# SCH_USB_hub_2024-10-11.net
KiCad netlist of a schematic drawn in EasyEDA
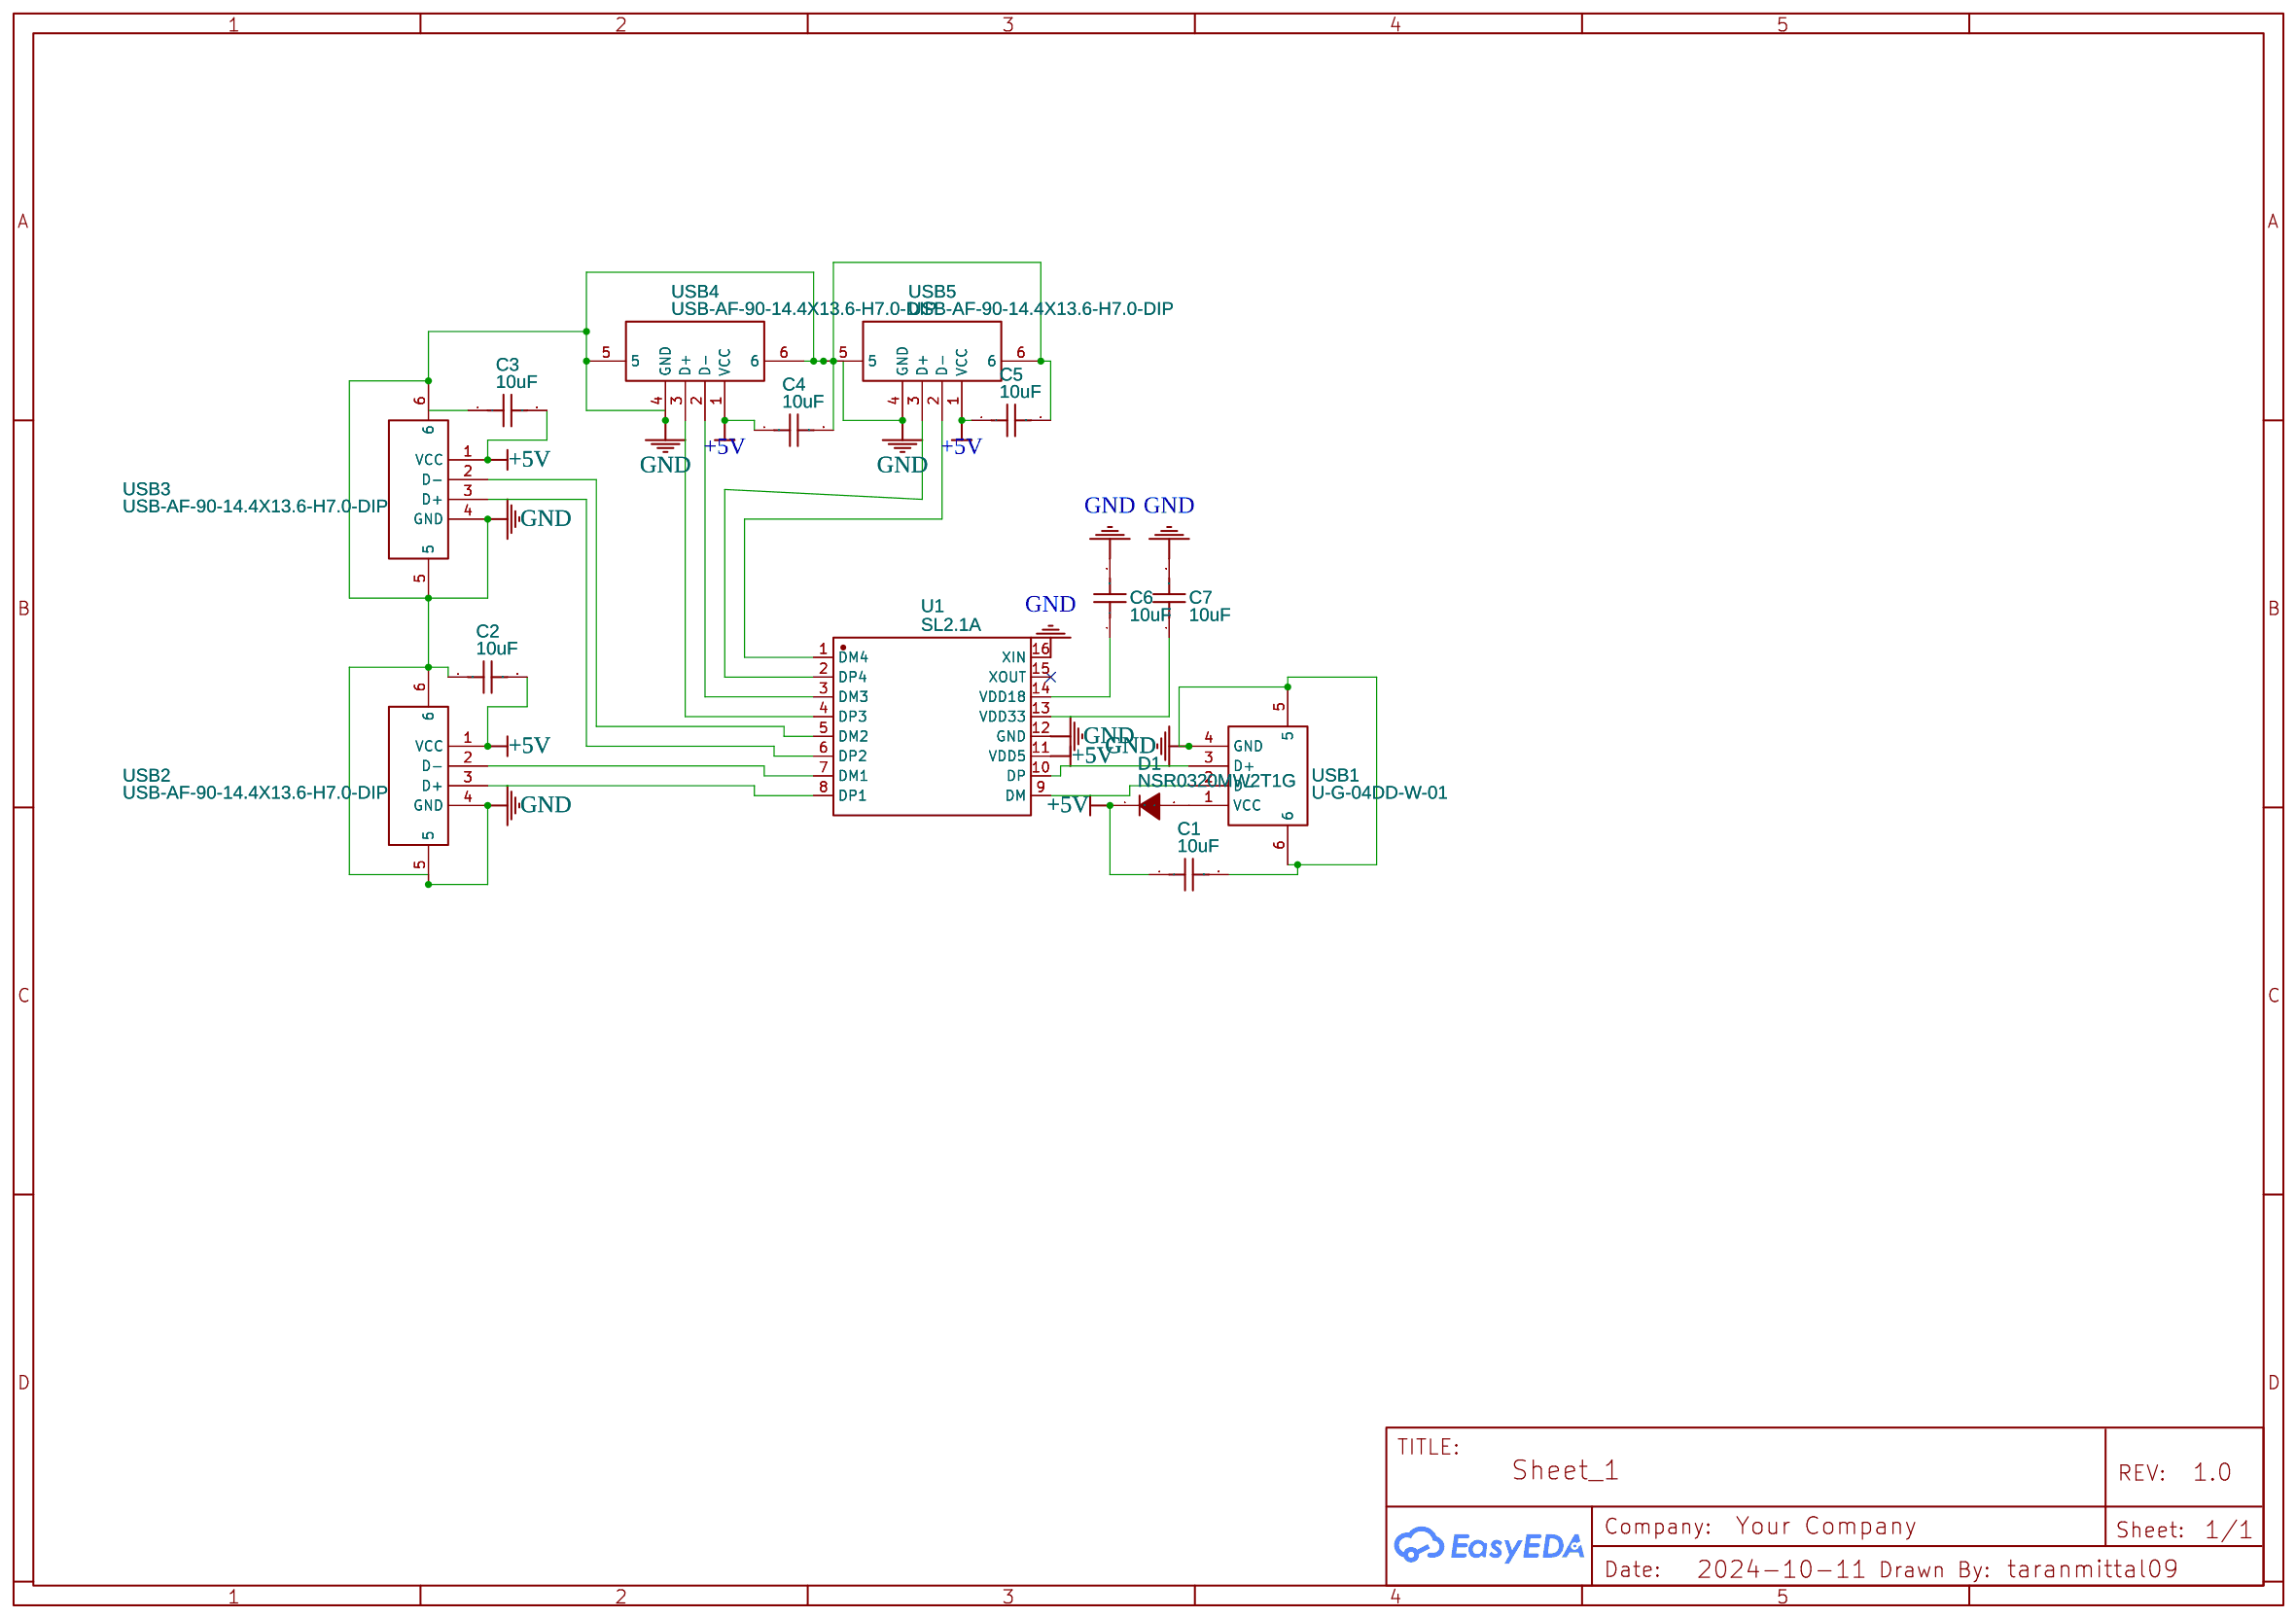
[diagram p0: schematic sheet]

(export (version "E")
  (design (tool "Eeschema 10.0.6"))
  (components
    (comp (ref "C1")
      (value "10uF")
      (fields
        (field (name "Manufacturer Part") "CL10A106KP8NNNC")
        (field (name "Manufacturer") "SAMSUNG(三星)")
      )
      (libsource (lib "") (part "CL10A106KP8NNNC"))
    )
    (comp (ref "C2")
      (value "10uF")
      (fields
        (field (name "Manufacturer Part") "CL10A106KP8NNNC")
        (field (name "Manufacturer") "SAMSUNG(三星)")
      )
      (libsource (lib "") (part "CL10A106KP8NNNC"))
    )
    (comp (ref "C3")
      (value "10uF")
      (fields
        (field (name "Manufacturer Part") "CL10A106KP8NNNC")
        (field (name "Manufacturer") "SAMSUNG(三星)")
      )
      (libsource (lib "") (part "CL10A106KP8NNNC"))
    )
    (comp (ref "C4")
      (value "10uF")
      (fields
        (field (name "Manufacturer Part") "CL10A106KP8NNNC")
        (field (name "Manufacturer") "SAMSUNG(三星)")
      )
      (libsource (lib "") (part "CL10A106KP8NNNC"))
    )
    (comp (ref "C5")
      (value "10uF")
      (fields
        (field (name "Manufacturer Part") "CL10A106KP8NNNC")
        (field (name "Manufacturer") "SAMSUNG(三星)")
      )
      (libsource (lib "") (part "CL10A106KP8NNNC"))
    )
    (comp (ref "C6")
      (value "10uF")
      (fields
        (field (name "Manufacturer Part") "CL10A106KP8NNNC")
        (field (name "Manufacturer") "SAMSUNG(三星)")
      )
      (libsource (lib "") (part "CL10A106KP8NNNC_1"))
    )
    (comp (ref "C7")
      (value "10uF")
      (fields
        (field (name "Manufacturer Part") "CL10A106KP8NNNC")
        (field (name "Manufacturer") "SAMSUNG(三星)")
      )
      (libsource (lib "") (part "CL10A106KP8NNNC_1"))
    )
    (comp (ref "D1")
      (value "NSR0320MW2T1G")
      (fields (field (name "Manufacturer") "onsemi(安森美)"))
      (libsource (lib "") (part "NSR0320MW2T1G"))
    )
    (comp (ref "U1")
      (value "SL2.1A")
      (fields (field (name "Manufacturer") "CoreChips(和芯润德)"))
      (libsource (lib "") (part "SL2.1A"))
    )
    (comp (ref "USB1")
      (value "U-G-04DD-W-01")
      (fields (field (name "Manufacturer Part") "U-G-O4DD-W-1") (field (name "Manufacturer") "韩国韩荣"))
      (libsource (lib "") (part "U-G-04DD-W-01"))
    )
    (comp (ref "USB2")
      (value "USB-AF-90-14.4X13.6-H7.0-DIP")
      (fields (field (name "Manufacturer Part") "903-131A1011D10100") (field (name "Manufacturer") "精拓金"))
      (libsource (lib "") (part "USB-AF-90-14.4X13.6-H7.0-DIP"))
    )
    (comp (ref "USB3")
      (value "USB-AF-90-14.4X13.6-H7.0-DIP")
      (fields (field (name "Manufacturer Part") "903-131A1011D10100") (field (name "Manufacturer") "精拓金"))
      (libsource (lib "") (part "USB-AF-90-14.4X13.6-H7.0-DIP"))
    )
    (comp (ref "USB4")
      (value "USB-AF-90-14.4X13.6-H7.0-DIP")
      (fields (field (name "Manufacturer Part") "903-131A1011D10100") (field (name "Manufacturer") "精拓金"))
      (libsource (lib "") (part "USB-AF-90-14.4X13.6-H7.0-DIP_1"))
    )
    (comp (ref "USB5")
      (value "USB-AF-90-14.4X13.6-H7.0-DIP")
      (fields (field (name "Manufacturer Part") "903-131A1011D10100") (field (name "Manufacturer") "精拓金"))
      (libsource (lib "") (part "USB-AF-90-14.4X13.6-H7.0-DIP_1"))
    )
  )
  (nets
    (net (code "1") (name "+5V") (class "Default")
      (node (ref "C1") (pin "1") (pinfunction "1_1") (pintype "unspecified"))
      (node (ref "C2") (pin "2") (pinfunction "2_2") (pintype "unspecified"))
      (node (ref "C3") (pin "2") (pinfunction "2_2") (pintype "unspecified"))
      (node (ref "C4") (pin "1") (pinfunction "1_1") (pintype "unspecified"))
      (node (ref "C5") (pin "1") (pinfunction "1_1") (pintype "unspecified"))
      (node (ref "D1") (pin "1") (pinfunction "C_1") (pintype "unspecified"))
      (node (ref "U1") (pin "11") (pinfunction "VDD5_11") (pintype "unspecified"))
      (node (ref "USB2") (pin "1") (pinfunction "VCC_1") (pintype "unspecified"))
      (node (ref "USB3") (pin "1") (pinfunction "VCC_1") (pintype "unspecified"))
      (node (ref "USB4") (pin "1") (pinfunction "VCC_1") (pintype "unspecified"))
      (node (ref "USB5") (pin "1") (pinfunction "VCC_1") (pintype "unspecified"))
    )
    (net (code "2") (name "GND") (class "Default")
      (node (ref "C1") (pin "2") (pinfunction "2_2") (pintype "unspecified"))
      (node (ref "C2") (pin "1") (pinfunction "1_1") (pintype "unspecified"))
      (node (ref "C3") (pin "1") (pinfunction "1_1") (pintype "unspecified"))
      (node (ref "C4") (pin "2") (pinfunction "2_2") (pintype "unspecified"))
      (node (ref "C5") (pin "2") (pinfunction "2_2") (pintype "unspecified"))
      (node (ref "C6") (pin "2") (pinfunction "2_2") (pintype "unspecified"))
      (node (ref "C7") (pin "2") (pinfunction "2_2") (pintype "unspecified"))
      (node (ref "U1") (pin "12") (pinfunction "GND_12") (pintype "unspecified"))
      (node (ref "U1") (pin "16") (pinfunction "XIN_16") (pintype "unspecified"))
      (node (ref "USB1") (pin "4") (pinfunction "GND_4") (pintype "unspecified"))
      (node (ref "USB1") (pin "5") (pinfunction "5_5") (pintype "unspecified"))
      (node (ref "USB1") (pin "6") (pinfunction "6_6") (pintype "unspecified"))
      (node (ref "USB2") (pin "4") (pinfunction "GND_4") (pintype "unspecified"))
      (node (ref "USB2") (pin "5") (pinfunction "5_5") (pintype "unspecified"))
      (node (ref "USB2") (pin "6") (pinfunction "6_6") (pintype "unspecified"))
      (node (ref "USB3") (pin "4") (pinfunction "GND_4") (pintype "unspecified"))
      (node (ref "USB3") (pin "5") (pinfunction "5_5") (pintype "unspecified"))
      (node (ref "USB3") (pin "6") (pinfunction "6_6") (pintype "unspecified"))
      (node (ref "USB4") (pin "4") (pinfunction "GND_4") (pintype "unspecified"))
      (node (ref "USB4") (pin "5") (pinfunction "5_5") (pintype "unspecified"))
      (node (ref "USB4") (pin "6") (pinfunction "6_6") (pintype "unspecified"))
      (node (ref "USB5") (pin "4") (pinfunction "GND_4") (pintype "unspecified"))
      (node (ref "USB5") (pin "5") (pinfunction "5_5") (pintype "unspecified"))
      (node (ref "USB5") (pin "6") (pinfunction "6_6") (pintype "unspecified"))
    )
    (net (code "3") (name "Net-(D1-A)") (class "Default")
      (node (ref "D1") (pin "2") (pinfunction "A_2") (pintype "unspecified"))
      (node (ref "USB1") (pin "1") (pinfunction "VCC_1") (pintype "unspecified"))
    )
    (net (code "4") (name "Net-(U1-DM)") (class "Default")
      (node (ref "U1") (pin "9") (pinfunction "DM_9") (pintype "unspecified"))
      (node (ref "USB1") (pin "2") (pinfunction "D-_2") (pintype "unspecified"))
    )
    (net (code "5") (name "Net-(U1-DM1)") (class "Default")
      (node (ref "U1") (pin "7") (pinfunction "DM1_7") (pintype "unspecified"))
      (node (ref "USB2") (pin "2") (pinfunction "D-_2") (pintype "unspecified"))
    )
    (net (code "6") (name "Net-(U1-DM2)") (class "Default")
      (node (ref "U1") (pin "5") (pinfunction "DM2_5") (pintype "unspecified"))
      (node (ref "USB3") (pin "2") (pinfunction "D-_2") (pintype "unspecified"))
    )
    (net (code "7") (name "Net-(U1-DM3)") (class "Default")
      (node (ref "U1") (pin "3") (pinfunction "DM3_3") (pintype "unspecified"))
      (node (ref "USB4") (pin "2") (pinfunction "D-_2") (pintype "unspecified"))
    )
    (net (code "8") (name "Net-(U1-DM4)") (class "Default")
      (node (ref "U1") (pin "1") (pinfunction "DM4_1") (pintype "unspecified"))
      (node (ref "USB5") (pin "2") (pinfunction "D-_2") (pintype "unspecified"))
    )
    (net (code "9") (name "Net-(U1-DP)") (class "Default")
      (node (ref "U1") (pin "10") (pinfunction "DP_10") (pintype "unspecified"))
      (node (ref "USB1") (pin "3") (pinfunction "D+_3") (pintype "unspecified"))
    )
    (net (code "10") (name "Net-(U1-DP1)") (class "Default")
      (node (ref "U1") (pin "8") (pinfunction "DP1_8") (pintype "unspecified"))
      (node (ref "USB2") (pin "3") (pinfunction "D+_3") (pintype "unspecified"))
    )
    (net (code "11") (name "Net-(U1-DP2)") (class "Default")
      (node (ref "U1") (pin "6") (pinfunction "DP2_6") (pintype "unspecified"))
      (node (ref "USB3") (pin "3") (pinfunction "D+_3") (pintype "unspecified"))
    )
    (net (code "12") (name "Net-(U1-DP3)") (class "Default")
      (node (ref "U1") (pin "4") (pinfunction "DP3_4") (pintype "unspecified"))
      (node (ref "USB4") (pin "3") (pinfunction "D+_3") (pintype "unspecified"))
    )
    (net (code "13") (name "Net-(U1-DP4)") (class "Default")
      (node (ref "U1") (pin "2") (pinfunction "DP4_2") (pintype "unspecified"))
      (node (ref "USB5") (pin "3") (pinfunction "D+_3") (pintype "unspecified"))
    )
    (net (code "14") (name "Net-(U1-VDD18)") (class "Default")
      (node (ref "C6") (pin "1") (pinfunction "1_1") (pintype "unspecified"))
      (node (ref "U1") (pin "14") (pinfunction "VDD18_14") (pintype "unspecified"))
    )
    (net (code "15") (name "Net-(U1-VDD33)") (class "Default")
      (node (ref "C7") (pin "1") (pinfunction "1_1") (pintype "unspecified"))
      (node (ref "U1") (pin "13") (pinfunction "VDD33_13") (pintype "unspecified"))
    )
    (net (code "16") (name "unconnected-(U1-XOUT-Pad15)") (class "Default")
      (node (ref "U1") (pin "15") (pinfunction "XOUT_15") (pintype "unspecified+no_connect"))
    )
  )
)
